# MicroController.net
KiCad netlist of a schematic drawn in Altium Designer
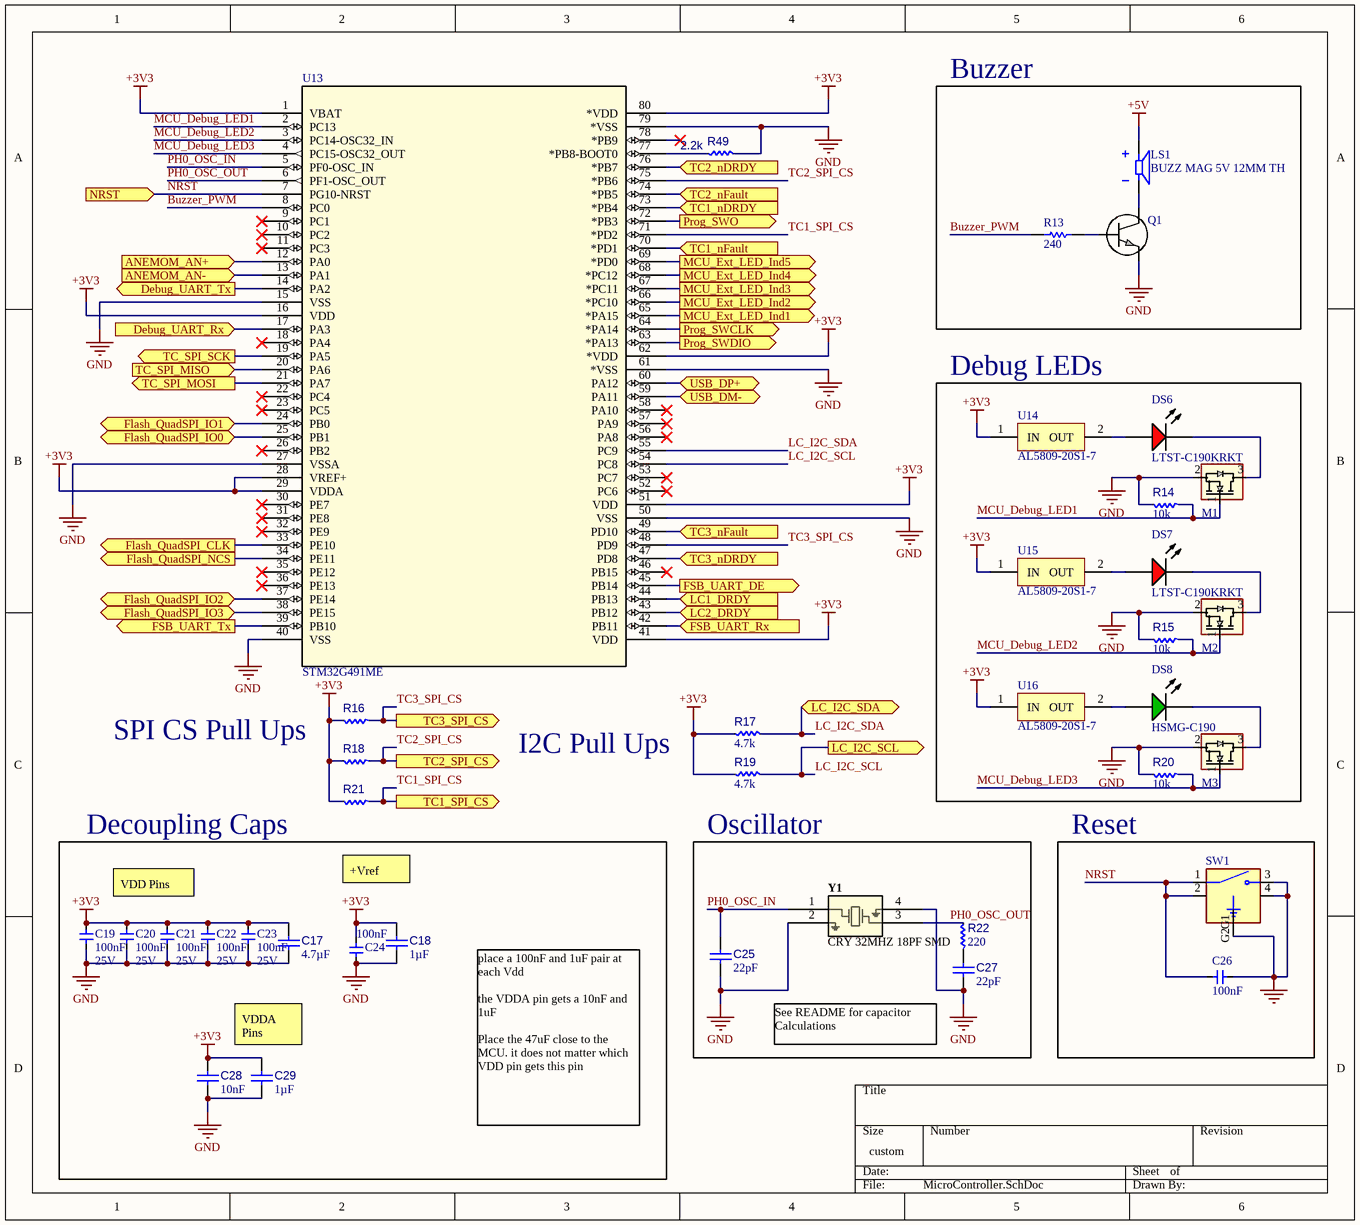
[diagram p0: MicroController.SchDoc]

(export (version "E")
  (design (tool "Eeschema 10.0.6"))
  (components
    (comp (ref "C17")
      (value "4.7µF")
      (footprint "Copy of CAPC0603(1608)100_L")
      (description "CC0603MRX5R6BB475 Chip Capacitor, 4.7µF +/-20%, 10V, 0603, Thickness 1 mm")
      (fields (field (name "TOLERANCE") "20%") (field (name "Comment") "CAP CER 4.7µF +/-20% 10V 0603"))
      (libsource (lib "University of Calgary - SOAR") (part "4.7uF"))
    )
    (comp (ref "C18")
      (value "1µF")
      (footprint "CAPC0402(1005)60_L")
      (description "Chip Capacitor, 1µF +/-20%, 10V, 0402, Thickness 0.6 mm")
      (fields (field (name "TOLERANCE") "10%") (field (name "Comment") "Capacitor 1µF +/-20% 10V 0402"))
      (libsource (lib "University of Calgary - SOAR") (part "CAP-NP-2"))
    )
    (comp (ref "C19")
      (value "100nF")
      (footprint "0.1uF-FP-CGA3E-0_3-0_1-IPC_A")
      (description "CGA3E2X7R1E104K080AA CAP CER 0.1UF 25V X7R 0603")
      (fields
        (field (name "MANUFACTURER") "TDK Corporation")
        (field (name "MANUFACTURER PART NUMBER") "CGA3E2X7R1E104K080AA")
        (field (name "VOLTAGE - RATED") "25V")
        (field (name "SOURCE") "PlumBay_SchLib.SchLib")
      )
      (libsource (lib "University of Calgary - SOAR") (part "100nF"))
    )
    (comp (ref "C20")
      (value "100nF")
      (footprint "0.1uF-FP-CGA3E-0_3-0_1-IPC_A")
      (description "CGA3E2X7R1E104K080AA CAP CER 0.1UF 25V X7R 0603")
      (fields
        (field (name "MANUFACTURER") "TDK Corporation")
        (field (name "MANUFACTURER PART NUMBER") "CGA3E2X7R1E104K080AA")
        (field (name "VOLTAGE - RATED") "25V")
        (field (name "SOURCE") "PlumBay_SchLib.SchLib")
      )
      (libsource (lib "University of Calgary - SOAR") (part "100nF"))
    )
    (comp (ref "C21")
      (value "100nF")
      (footprint "0.1uF-FP-CGA3E-0_3-0_1-IPC_A")
      (description "CGA3E2X7R1E104K080AA CAP CER 0.1UF 25V X7R 0603")
      (fields
        (field (name "MANUFACTURER") "TDK Corporation")
        (field (name "MANUFACTURER PART NUMBER") "CGA3E2X7R1E104K080AA")
        (field (name "VOLTAGE - RATED") "25V")
        (field (name "SOURCE") "PlumBay_SchLib.SchLib")
      )
      (libsource (lib "University of Calgary - SOAR") (part "100nF"))
    )
    (comp (ref "C22")
      (value "100nF")
      (footprint "0.1uF-FP-CGA3E-0_3-0_1-IPC_A")
      (description "CGA3E2X7R1E104K080AA CAP CER 0.1UF 25V X7R 0603")
      (fields
        (field (name "MANUFACTURER") "TDK Corporation")
        (field (name "MANUFACTURER PART NUMBER") "CGA3E2X7R1E104K080AA")
        (field (name "VOLTAGE - RATED") "25V")
        (field (name "SOURCE") "PlumBay_SchLib.SchLib")
      )
      (libsource (lib "University of Calgary - SOAR") (part "100nF"))
    )
    (comp (ref "C23")
      (value "100nF")
      (footprint "0.1uF-FP-CGA3E-0_3-0_1-IPC_A")
      (description "CGA3E2X7R1E104K080AA CAP CER 0.1UF 25V X7R 0603")
      (fields
        (field (name "MANUFACTURER") "TDK Corporation")
        (field (name "MANUFACTURER PART NUMBER") "CGA3E2X7R1E104K080AA")
        (field (name "VOLTAGE - RATED") "25V")
        (field (name "SOURCE") "PlumBay_SchLib.SchLib")
      )
      (libsource (lib "University of Calgary - SOAR") (part "100nF"))
    )
    (comp (ref "C24")
      (value "100nF")
      (footprint "0.1uF-FP-CGA3E-0_3-0_1-IPC_A")
      (description "CGA3E2X7R1E104K080AA CAP CER 0.1UF 25V X7R 0603")
      (fields
        (field (name "TOLERANCE") "10%")
        (field (name "MANUFACTURER") "TDK Corporation")
        (field (name "SOURCE") "PlumBay_SchLib.SchLib")
      )
      (libsource (lib "University of Calgary - SOAR") (part "100nF"))
    )
    (comp (ref "C25")
      (value "22pF")
      (footprint "CAP_0603_LD")
      (description "GRM1885C1H220JA01D - 22 pF ±5% 50V Ceramic Capacitor C0G, NP0 0603 (1608 Metric)")
      (fields (field (name "TOLERANCE") "5%") (field (name "VOLTAGE") "50V"))
      (libsource (lib "University of Calgary - SOAR") (part "CAP-NP-2"))
    )
    (comp (ref "C26")
      (value "100nF")
      (footprint "0.1uF-FP-CGA3E-0_3-0_1-IPC_A")
      (description "CGA3E2X7R1E104K080AA CAP CER 0.1UF 25V X7R 0603")
      (fields
        (field (name "TOLERANCE") "10%")
        (field (name "MANUFACTURER") "TDK Corporation")
        (field (name "SOURCE") "PlumBay_SchLib.SchLib")
      )
      (libsource (lib "University of Calgary - SOAR") (part "100nF"))
    )
    (comp (ref "C27")
      (value "22pF")
      (footprint "CAP_0603_LD")
      (description "GRM1885C1H220JA01D - 22 pF ±5% 50V Ceramic Capacitor C0G, NP0 0603 (1608 Metric)")
      (fields (field (name "TOLERANCE") "5%") (field (name "VOLTAGE") "50V"))
      (libsource (lib "University of Calgary - SOAR") (part "CAP-NP-2"))
    )
    (comp (ref "C28")
      (value "10nF")
      (footprint "CAP_0603")
      (description "C0603C103K5RACTU - Multilayer Ceramic Capacitors Mlcc - Smd/Smt 50V 0.01Uf X7R 0603 10%")
      (fields (field (name "TOLERANCE") "10%") (field (name "Comment") "CAP CER 10nF 50V 10% 0603"))
      (libsource (lib "University of Calgary - SOAR") (part "CAP-NP-2"))
    )
    (comp (ref "C29")
      (value "1µF")
      (footprint "CAPC0402(1005)60_L")
      (description "Chip Capacitor, 1µF +/-20%, 10V, 0402, Thickness 0.6 mm")
      (fields (field (name "TOLERANCE") "10%") (field (name "Comment") "Capacitor 1µF +/-20% 10V 0402"))
      (libsource (lib "University of Calgary - SOAR") (part "CAP-NP-2"))
    )
    (comp (ref "DS6")
      (value "LTST-C190KRKT")
      (footprint "LTST-C191KRKT_V")
      (description "LED Uni-Color Red, 62.5 mW, 25 mA, -30 to 85 degC, 2-Pin SMD, RoHS, Tape and Reel")
      (fields (field (name "POWER") "75mW") (field (name "MANUFACTURER") "Lite-On"))
      (libsource (lib "University of Calgary - SOAR") (part "LED-RED-AK-2"))
    )
    (comp (ref "DS7")
      (value "LTST-C190KRKT")
      (footprint "LTST-C191KRKT_V")
      (description "LED Uni-Color Red, 62.5 mW, 25 mA, -30 to 85 degC, 2-Pin SMD, RoHS, Tape and Reel")
      (fields (field (name "POWER") "75mW") (field (name "MANUFACTURER") "Lite-On"))
      (libsource (lib "University of Calgary - SOAR") (part "LED-RED-AK-2"))
    )
    (comp (ref "DS8")
      (value "HSMG-C190")
      (footprint "AVAG-HSMX-C190_V")
      (description "LED Uni-Color Green, 52 mW, 20 mA, -40 to 85 degC, 2-Pin SMD, RoHS, Tape and Reel")
      (fields (field (name "POWER") "52mW") (field (name "MANUFACTURER") "Avago"))
      (libsource (lib "University of Calgary - SOAR") (part "LED-GREEN-AK-2"))
    )
    (comp (ref "LS1")
      (value "BUZZ MAG 5V 12MM TH")
      (footprint "CMI-1210-5-95T-Footprint-1")
      (description "CMI-1210-5-95T 12 mm, 5 Vdc, 98 dB, Through Hole, Magnetic Audio Indicator Buzzer CMI-1210-5-95T")
      (libsource (lib "University of Calgary - SOAR") (part "CMI-1210-5-95T-Symbol-1"))
    )
    (comp (ref "M1")
      (value "MOS NMOS 30V 5.6A SOT-23")
      (footprint "PJA3404_R1_00001-Footprint-1")
      (libsource (lib "University of Calgary - SOAR") (part "TRANS-NPN-3"))
    )
    (comp (ref "M2")
      (value "MOS NMOS 30V 5.6A SOT-23")
      (footprint "PJA3404_R1_00001-Footprint-1")
      (libsource (lib "University of Calgary - SOAR") (part "TRANS-NPN-3"))
    )
    (comp (ref "M3")
      (value "MOS NMOS 30V 5.6A SOT-23")
      (footprint "PJA3404_R1_00001-Footprint-1")
      (libsource (lib "University of Calgary - SOAR") (part "TRANS-NPN-3"))
    )
    (comp (ref "Q1")
      (value "NPN 350mW 40V 200mA")
      (footprint "MMBT3904-TP-Footprint-1")
      (description "Transistor, Bipolar, Si, NPN, Amplifier, Small Signal, Vceo 40VDC, IC 200MA, Pd 350MW")
      (libsource (lib "University of Calgary - SOAR") (part "MMBT3904-TP-Symbol-1"))
    )
    (comp (ref "R13")
      (value "240")
      (footprint "RESC1005X40X25ML05T05")
      (description "Chip Resistor, 240 Ohm, +/- 5%, 100 mW, -55 to 155 degC, 0402 (1005 Metric), RoHS, Tape and Reel")
      (fields
        (field (name "PARTNUMBER") "ERJ-2GEJ241x")
        (field (name "TOLERANCE") "5%")
        (field (name "SOURCE") "PC4-SODIMM_V200_RC_A1_20141015.SCHLIB")
      )
      (libsource (lib "University of Calgary - SOAR") (part "CMP-2004-03155-3"))
    )
    (comp (ref "R14")
      (value "10k")
      (footprint "RESC2013X50X35ML15T15")
      (description "Chip Resistor, 10 KOhm, +/- 1%, 125 mW, -55 to 155 degC, 0805 (2012 Metric)")
      (fields (field (name "POWER") "125mW") (field (name "TOLERANCE") "1%"))
      (libsource (lib "University of Calgary - SOAR") (part "RES-2"))
    )
    (comp (ref "R15")
      (value "10k")
      (footprint "RESC2013X50X35ML15T15")
      (description "Chip Resistor, 10 KOhm, +/- 1%, 125 mW, -55 to 155 degC, 0805 (2012 Metric)")
      (fields (field (name "POWER") "125mW") (field (name "TOLERANCE") "1%"))
      (libsource (lib "University of Calgary - SOAR") (part "RES-2"))
    )
    (comp (ref "R16")
      (value "CRGCQ0603F2K2")
      (footprint "FP-CRGCQ0603-IPC_A")
      (libsource (lib "University of Calgary - SOAR") (part "RES-2"))
    )
    (comp (ref "R17")
      (value "4.7k")
      (footprint "RESC2013X70X40ML20T20")
      (description "Chip Resistor, 4.7 KOhm, +/- 1%, 0.125 W, -55 to 155 degC, 0805 (2012 Metric)")
      (fields (field (name "POWER") "125mW") (field (name "TOLERANCE") "1%"))
      (libsource (lib "University of Calgary - SOAR") (part "RES-2"))
    )
    (comp (ref "R18")
      (value "CRGCQ0603F2K2")
      (footprint "FP-CRGCQ0603-IPC_A")
      (libsource (lib "University of Calgary - SOAR") (part "RES-2"))
    )
    (comp (ref "R19")
      (value "4.7k")
      (footprint "RESC2013X70X40ML20T20")
      (description "Chip Resistor, 4.7 KOhm, +/- 1%, 0.125 W, -55 to 155 degC, 0805 (2012 Metric)")
      (fields (field (name "POWER") "125mW") (field (name "TOLERANCE") "1%"))
      (libsource (lib "University of Calgary - SOAR") (part "RES-2"))
    )
    (comp (ref "R20")
      (value "10k")
      (footprint "RESC2013X50X35ML15T15")
      (description "Chip Resistor, 10 KOhm, +/- 1%, 125 mW, -55 to 155 degC, 0805 (2012 Metric)")
      (fields (field (name "POWER") "125mW") (field (name "TOLERANCE") "1%"))
      (libsource (lib "University of Calgary - SOAR") (part "RES-2"))
    )
    (comp (ref "R21")
      (value "CRGCQ0603F2K2")
      (footprint "FP-CRGCQ0603-IPC_A")
      (libsource (lib "University of Calgary - SOAR") (part "RES-2"))
    )
    (comp (ref "R22")
      (value "220")
      (footprint "RES_0603_LD")
      (fields (field (name "Comment") "RES 220R 5% 100mW 0603"))
      (libsource (lib "University of Calgary - SOAR") (part "RES-2"))
    )
    (comp (ref "R49")
      (value "2.2k")
      (footprint "FP-CRGCQ0603-IPC_A")
      (libsource (lib "University of Calgary - SOAR") (part "RES-2"))
    )
    (comp (ref "SW1")
      (value "BTN 12V 0.05A PTS526SMG15SMTR2 LFS")
      (footprint "PTS526SMG15SMTR2-Footprint-1")
      (libsource (lib "University of Calgary - SOAR") (part "PTS526SMG15SMTR2-Symbol-1"))
    )
    (comp (ref "U13")
      (value "STM32G491ME")
      (footprint "STM32G491ME-Footprint-1")
      (description "MCU 32-Bit ARM Cortex-M4 RISC 512kByte Flash 1.71V to 3.6V 80-Pin LQFP Tray")
      (libsource (lib "University of Calgary - SOAR") (part "STM32G491ME-Symbol-1"))
    )
    (comp (ref "U14")
      (value "AL5809-20S1-7")
      (footprint "DIOD-SOD123-A_V")
      (description "Led Driver, Cc/Linear, -40 To 125Deg C Rohs Compliant: Yes")
      (libsource (lib "University of Calgary - SOAR") (part "DIOD-AL5809-2"))
    )
    (comp (ref "U15")
      (value "AL5809-20S1-7")
      (footprint "DIOD-SOD123-A_V")
      (description "Led Driver, Cc/Linear, -40 To 125Deg C Rohs Compliant: Yes")
      (libsource (lib "University of Calgary - SOAR") (part "DIOD-AL5809-2"))
    )
    (comp (ref "U16")
      (value "AL5809-20S1-7")
      (footprint "DIOD-SOD123-A_V")
      (description "Led Driver, Cc/Linear, -40 To 125Deg C Rohs Compliant: Yes")
      (libsource (lib "University of Calgary - SOAR") (part "DIOD-AL5809-2"))
    )
    (comp (ref "Y1")
      (value "CRY 32MHZ 18PF SMD")
      (footprint "ABM8-32.000MHZ-B2-T-Footprint-1")
      (description "Crystal 32MHz ±20ppm (Tol) ±50ppm (Stability) 18pF FUND 40Ohm 4-Pin Ultra Mini-CSMD T/R")
      (libsource (lib "University of Calgary - SOAR") (part "E7343LF"))
    )
  )
  (nets
    (net (code "1") (name "+3V3") (class "Default")
      (node (ref "C17") (pin "2") (pinfunction "2_2") (pintype "passive"))
      (node (ref "C18") (pin "2") (pinfunction "2_2") (pintype "passive"))
      (node (ref "C19") (pin "2") (pinfunction "2_2") (pintype "passive"))
      (node (ref "C20") (pin "2") (pinfunction "2_2") (pintype "passive"))
      (node (ref "C21") (pin "2") (pinfunction "2_2") (pintype "passive"))
      (node (ref "C22") (pin "2") (pinfunction "2_2") (pintype "passive"))
      (node (ref "C23") (pin "2") (pinfunction "2_2") (pintype "passive"))
      (node (ref "C24") (pin "2") (pinfunction "2_2") (pintype "passive"))
      (node (ref "C28") (pin "2") (pinfunction "2_2") (pintype "passive"))
      (node (ref "C29") (pin "2") (pinfunction "2_2") (pintype "passive"))
      (node (ref "R16") (pin "2") (pinfunction "2_2") (pintype "passive"))
      (node (ref "R17") (pin "1") (pinfunction "1_1") (pintype "passive"))
      (node (ref "R18") (pin "2") (pinfunction "2_2") (pintype "passive"))
      (node (ref "R19") (pin "1") (pinfunction "1_1") (pintype "passive"))
      (node (ref "R21") (pin "2") (pinfunction "2_2") (pintype "passive"))
      (node (ref "U13") (pin "1") (pinfunction "VBAT_1") (pintype "passive"))
      (node (ref "U13") (pin "16") (pinfunction "VDD_16") (pintype "power_in"))
      (node (ref "U13") (pin "28") (pinfunction "VREF+_28") (pintype "power_in"))
      (node (ref "U13") (pin "29") (pinfunction "VDDA_29") (pintype "power_in"))
      (node (ref "U13") (pin "41") (pinfunction "VDD_41") (pintype "power_in"))
      (node (ref "U13") (pin "51") (pinfunction "VDD_51") (pintype "power_in"))
      (node (ref "U13") (pin "62") (pinfunction "*VDD_62") (pintype "power_in"))
      (node (ref "U13") (pin "80") (pinfunction "*VDD_80") (pintype "power_in"))
      (node (ref "U14") (pin "1") (pinfunction "IN_1") (pintype "passive"))
      (node (ref "U15") (pin "1") (pinfunction "IN_1") (pintype "passive"))
      (node (ref "U16") (pin "1") (pinfunction "IN_1") (pintype "passive"))
    )
    (net (code "2") (name "+5V") (class "Default")
      (node (ref "LS1") (pin "P") (pinfunction "P_P") (pintype "passive"))
    )
    (net (code "3") (name "/ANEMOM_AN+") (class "Default")
      (node (ref "U13") (pin "12") (pinfunction "PA0_12") (pintype "bidirectional"))
    )
    (net (code "4") (name "/ANEMOM_AN-") (class "Default")
      (node (ref "U13") (pin "13") (pinfunction "PA1_13") (pintype "bidirectional"))
    )
    (net (code "5") (name "/Buzzer_PWM") (class "Default")
      (node (ref "R13") (pin "1") (pinfunction "1_1") (pintype "passive"))
      (node (ref "U13") (pin "8") (pinfunction "PC0_8") (pintype "bidirectional"))
    )
    (net (code "6") (name "/Debug_UART_Rx") (class "Default")
      (node (ref "U13") (pin "17") (pinfunction "PA3_17") (pintype "bidirectional"))
    )
    (net (code "7") (name "/Debug_UART_Tx") (class "Default")
      (node (ref "U13") (pin "14") (pinfunction "PA2_14") (pintype "bidirectional"))
    )
    (net (code "8") (name "/FSB_UART_DE") (class "Default")
      (node (ref "U13") (pin "45") (pinfunction "PB14_45") (pintype "bidirectional"))
    )
    (net (code "9") (name "/FSB_UART_Rx") (class "Default")
      (node (ref "U13") (pin "42") (pinfunction "PB11_42") (pintype "bidirectional"))
    )
    (net (code "10") (name "/FSB_UART_Tx") (class "Default")
      (node (ref "U13") (pin "39") (pinfunction "PB10_39") (pintype "bidirectional"))
    )
    (net (code "11") (name "/Flash_QuadSPI_CLK") (class "Default")
      (node (ref "U13") (pin "33") (pinfunction "PE10_33") (pintype "bidirectional"))
    )
    (net (code "12") (name "/Flash_QuadSPI_IO0") (class "Default")
      (node (ref "U13") (pin "25") (pinfunction "PB1_25") (pintype "bidirectional"))
    )
    (net (code "13") (name "/Flash_QuadSPI_IO1") (class "Default")
      (node (ref "U13") (pin "24") (pinfunction "PB0_24") (pintype "bidirectional"))
    )
    (net (code "14") (name "/Flash_QuadSPI_IO2") (class "Default")
      (node (ref "U13") (pin "37") (pinfunction "PE14_37") (pintype "bidirectional"))
    )
    (net (code "15") (name "/Flash_QuadSPI_IO3") (class "Default")
      (node (ref "U13") (pin "38") (pinfunction "PE15_38") (pintype "bidirectional"))
    )
    (net (code "16") (name "/Flash_QuadSPI_NCS") (class "Default")
      (node (ref "U13") (pin "34") (pinfunction "PE11_34") (pintype "bidirectional"))
    )
    (net (code "17") (name "/LC1_DRDY") (class "Default")
      (node (ref "U13") (pin "44") (pinfunction "PB13_44") (pintype "bidirectional"))
    )
    (net (code "18") (name "/LC2_DRDY") (class "Default")
      (node (ref "U13") (pin "43") (pinfunction "PB12_43") (pintype "bidirectional"))
    )
    (net (code "19") (name "/LC_I2C_SCL") (class "Default")
      (node (ref "R19") (pin "2") (pinfunction "2_2") (pintype "passive"))
      (node (ref "U13") (pin "54") (pinfunction "PC8_54") (pintype "bidirectional"))
    )
    (net (code "20") (name "/LC_I2C_SDA") (class "Default")
      (node (ref "R17") (pin "2") (pinfunction "2_2") (pintype "passive"))
      (node (ref "U13") (pin "55") (pinfunction "PC9_55") (pintype "bidirectional"))
    )
    (net (code "21") (name "/MCU_Debug_LED1") (class "Default")
      (node (ref "M1") (pin "1") (pinfunction "1_1") (pintype "passive"))
      (node (ref "R14") (pin "1") (pinfunction "1_1") (pintype "passive"))
      (node (ref "U13") (pin "2") (pinfunction "PC13_2") (pintype "bidirectional"))
    )
    (net (code "22") (name "/MCU_Debug_LED2") (class "Default")
      (node (ref "M2") (pin "1") (pinfunction "1_1") (pintype "passive"))
      (node (ref "R15") (pin "1") (pinfunction "1_1") (pintype "passive"))
      (node (ref "U13") (pin "3") (pinfunction "PC14-OSC32_IN_3") (pintype "bidirectional"))
    )
    (net (code "23") (name "/MCU_Debug_LED3") (class "Default")
      (node (ref "M3") (pin "1") (pinfunction "1_1") (pintype "passive"))
      (node (ref "R20") (pin "1") (pinfunction "1_1") (pintype "passive"))
      (node (ref "U13") (pin "4") (pinfunction "PC15-OSC32_OUT_4") (pintype "output"))
    )
    (net (code "24") (name "/MCU_Ext_LED_Ind1") (class "Default")
      (node (ref "U13") (pin "65") (pinfunction "*PA15_65") (pintype "bidirectional"))
    )
    (net (code "25") (name "/MCU_Ext_LED_Ind2") (class "Default")
      (node (ref "U13") (pin "66") (pinfunction "*PC10_66") (pintype "bidirectional"))
    )
    (net (code "26") (name "/MCU_Ext_LED_Ind3") (class "Default")
      (node (ref "U13") (pin "67") (pinfunction "*PC11_67") (pintype "bidirectional"))
    )
    (net (code "27") (name "/MCU_Ext_LED_Ind4") (class "Default")
      (node (ref "U13") (pin "68") (pinfunction "*PC12_68") (pintype "bidirectional"))
    )
    (net (code "28") (name "/MCU_Ext_LED_Ind5") (class "Default")
      (node (ref "U13") (pin "69") (pinfunction "*PD0_69") (pintype "bidirectional"))
    )
    (net (code "29") (name "/NRST") (class "Default")
      (node (ref "C26") (pin "2") (pinfunction "2_2") (pintype "passive"))
      (node (ref "SW1") (pin "1") (pinfunction "COM_1") (pintype "passive"))
      (node (ref "SW1") (pin "2") (pinfunction "COM_2") (pintype "passive"))
      (node (ref "U13") (pin "7") (pinfunction "PG10-NRST_7") (pintype "passive"))
    )
    (net (code "30") (name "/PH0_OSC_IN") (class "Default")
      (node (ref "C25") (pin "2") (pinfunction "2_2") (pintype "passive"))
      (node (ref "U13") (pin "5") (pinfunction "PF0-OSC_IN_5") (pintype "bidirectional"))
      (node (ref "Y1") (pin "1") (pinfunction "1_1") (pintype "passive"))
    )
    (net (code "31") (name "/PH0_OSC_OUT") (class "Default")
      (node (ref "R22") (pin "2") (pinfunction "2_2") (pintype "passive"))
      (node (ref "U13") (pin "6") (pinfunction "PF1-OSC_OUT_6") (pintype "output"))
      (node (ref "Y1") (pin "3") (pinfunction "3_3") (pintype "passive"))
    )
    (net (code "32") (name "/Prog_SWCLK") (class "Default")
      (node (ref "U13") (pin "64") (pinfunction "*PA14_64") (pintype "bidirectional"))
    )
    (net (code "33") (name "/Prog_SWDIO") (class "Default")
      (node (ref "U13") (pin "63") (pinfunction "*PA13_63") (pintype "bidirectional"))
    )
    (net (code "34") (name "/Prog_SWO") (class "Default")
      (node (ref "U13") (pin "72") (pinfunction "*PB3_72") (pintype "bidirectional"))
    )
    (net (code "35") (name "/TC1_SPI_CS") (class "Default")
      (node (ref "R21") (pin "1") (pinfunction "1_1") (pintype "passive"))
      (node (ref "U13") (pin "71") (pinfunction "*PD2_71") (pintype "bidirectional"))
    )
    (net (code "36") (name "/TC1_nDRDY") (class "Default")
      (node (ref "U13") (pin "73") (pinfunction "*PB4_73") (pintype "bidirectional"))
    )
    (net (code "37") (name "/TC1_nFault") (class "Default")
      (node (ref "U13") (pin "70") (pinfunction "*PD1_70") (pintype "bidirectional"))
    )
    (net (code "38") (name "/TC2_SPI_CS") (class "Default")
      (node (ref "R18") (pin "1") (pinfunction "1_1") (pintype "passive"))
      (node (ref "U13") (pin "75") (pinfunction "*PB6_75") (pintype "bidirectional"))
    )
    (net (code "39") (name "/TC2_nDRDY") (class "Default")
      (node (ref "U13") (pin "76") (pinfunction "*PB7_76") (pintype "bidirectional"))
    )
    (net (code "40") (name "/TC2_nFault") (class "Default")
      (node (ref "U13") (pin "74") (pinfunction "*PB5_74") (pintype "bidirectional"))
    )
    (net (code "41") (name "/TC3_SPI_CS") (class "Default")
      (node (ref "R16") (pin "1") (pinfunction "1_1") (pintype "passive"))
      (node (ref "U13") (pin "48") (pinfunction "PD9_48") (pintype "bidirectional"))
    )
    (net (code "42") (name "/TC3_nDRDY") (class "Default")
      (node (ref "U13") (pin "47") (pinfunction "PD8_47") (pintype "bidirectional"))
    )
    (net (code "43") (name "/TC3_nFault") (class "Default")
      (node (ref "U13") (pin "49") (pinfunction "PD10_49") (pintype "bidirectional"))
    )
    (net (code "44") (name "/TC_SPI_MISO") (class "Default")
      (node (ref "U13") (pin "20") (pinfunction "PA6_20") (pintype "bidirectional"))
    )
    (net (code "45") (name "/TC_SPI_MOSI") (class "Default")
      (node (ref "U13") (pin "21") (pinfunction "PA7_21") (pintype "bidirectional"))
    )
    (net (code "46") (name "/TC_SPI_SCK") (class "Default")
      (node (ref "U13") (pin "19") (pinfunction "PA5_19") (pintype "bidirectional"))
    )
    (net (code "47") (name "/USB_DM-") (class "Default")
      (node (ref "U13") (pin "59") (pinfunction "PA11_59") (pintype "bidirectional"))
    )
    (net (code "48") (name "/USB_DP+") (class "Default")
      (node (ref "U13") (pin "60") (pinfunction "PA12_60") (pintype "bidirectional"))
    )
    (net (code "49") (name "GND") (class "Default")
      (node (ref "C17") (pin "1") (pinfunction "1_1") (pintype "passive"))
      (node (ref "C18") (pin "1") (pinfunction "1_1") (pintype "passive"))
      (node (ref "C19") (pin "1") (pinfunction "1_1") (pintype "passive"))
      (node (ref "C20") (pin "1") (pinfunction "1_1") (pintype "passive"))
      (node (ref "C21") (pin "1") (pinfunction "1_1") (pintype "passive"))
      (node (ref "C22") (pin "1") (pinfunction "1_1") (pintype "passive"))
      (node (ref "C23") (pin "1") (pinfunction "1_1") (pintype "passive"))
      (node (ref "C24") (pin "1") (pinfunction "1_1") (pintype "passive"))
      (node (ref "C25") (pin "1") (pinfunction "1_1") (pintype "passive"))
      (node (ref "C26") (pin "1") (pinfunction "1_1") (pintype "passive"))
      (node (ref "C27") (pin "1") (pinfunction "1_1") (pintype "passive"))
      (node (ref "C28") (pin "1") (pinfunction "1_1") (pintype "passive"))
      (node (ref "C29") (pin "1") (pinfunction "1_1") (pintype "passive"))
      (node (ref "M1") (pin "2") (pinfunction "2_2") (pintype "passive"))
      (node (ref "M2") (pin "2") (pinfunction "2_2") (pintype "passive"))
      (node (ref "M3") (pin "2") (pinfunction "2_2") (pintype "passive"))
      (node (ref "Q1") (pin "2") (pinfunction "C_2") (pintype "passive"))
      (node (ref "R14") (pin "2") (pinfunction "2_2") (pintype "passive"))
      (node (ref "R15") (pin "2") (pinfunction "2_2") (pintype "passive"))
      (node (ref "R20") (pin "2") (pinfunction "2_2") (pintype "passive"))
      (node (ref "R49") (pin "2") (pinfunction "2_2") (pintype "passive"))
      (node (ref "SW1") (pin "3") (pinfunction "NO_3") (pintype "passive"))
      (node (ref "SW1") (pin "4") (pinfunction "NO_4") (pintype "passive"))
      (node (ref "SW1") (pin "G2") (pinfunction "GND_G2") (pintype "power_in"))
      (node (ref "U13") (pin "15") (pinfunction "VSS_15") (pintype "power_in"))
      (node (ref "U13") (pin "27") (pinfunction "VSSA_27") (pintype "power_in"))
      (node (ref "U13") (pin "40") (pinfunction "VSS_40") (pintype "power_in"))
      (node (ref "U13") (pin "50") (pinfunction "VSS_50") (pintype "power_in"))
      (node (ref "U13") (pin "61") (pinfunction "*VSS_61") (pintype "power_in"))
      (node (ref "U13") (pin "79") (pinfunction "*VSS_79") (pintype "power_in"))
      (node (ref "Y1") (pin "2") (pinfunction "2_2") (pintype "passive"))
      (node (ref "Y1") (pin "4") (pinfunction "4_4") (pintype "passive"))
    )
    (net (code "50") (name "Net-(C27-Pad2)") (class "Default")
      (node (ref "C27") (pin "2") (pinfunction "2_2") (pintype "passive"))
      (node (ref "R22") (pin "1") (pinfunction "1_1") (pintype "passive"))
    )
    (net (code "51") (name "Net-(DS6-A)") (class "Default")
      (node (ref "DS6") (pin "1") (pinfunction "A_1") (pintype "passive"))
      (node (ref "U14") (pin "2") (pinfunction "OUT_2") (pintype "passive"))
    )
    (net (code "52") (name "Net-(DS6-K)") (class "Default")
      (node (ref "DS6") (pin "2") (pinfunction "K_2") (pintype "passive"))
      (node (ref "M1") (pin "3") (pinfunction "3_3") (pintype "passive"))
    )
    (net (code "53") (name "Net-(DS7-A)") (class "Default")
      (node (ref "DS7") (pin "1") (pinfunction "A_1") (pintype "passive"))
      (node (ref "U15") (pin "2") (pinfunction "OUT_2") (pintype "passive"))
    )
    (net (code "54") (name "Net-(DS7-K)") (class "Default")
      (node (ref "DS7") (pin "2") (pinfunction "K_2") (pintype "passive"))
      (node (ref "M2") (pin "3") (pinfunction "3_3") (pintype "passive"))
    )
    (net (code "55") (name "Net-(DS8-A)") (class "Default")
      (node (ref "DS8") (pin "1") (pinfunction "A_1") (pintype "passive"))
      (node (ref "U16") (pin "2") (pinfunction "OUT_2") (pintype "passive"))
    )
    (net (code "56") (name "Net-(DS8-K)") (class "Default")
      (node (ref "DS8") (pin "2") (pinfunction "K_2") (pintype "passive"))
      (node (ref "M3") (pin "3") (pinfunction "3_3") (pintype "passive"))
    )
    (net (code "57") (name "Net-(Q1-B)") (class "Default")
      (node (ref "Q1") (pin "1") (pinfunction "B_1") (pintype "passive"))
      (node (ref "R13") (pin "2") (pinfunction "2_2") (pintype "passive"))
    )
    (net (code "58") (name "Net-(Q1-E)") (class "Default")
      (node (ref "LS1") (pin "N") (pinfunction "N_N") (pintype "passive"))
      (node (ref "Q1") (pin "3") (pinfunction "E_3") (pintype "passive"))
    )
    (net (code "59") (name "Net-(U13-*PB8-BOOT0)") (class "Default")
      (node (ref "R49") (pin "1") (pinfunction "1_1") (pintype "passive"))
      (node (ref "U13") (pin "77") (pinfunction "*PB8-BOOT0_77") (pintype "bidirectional"))
    )
    (net (code "60") (name "unconnected-(SW1-GND-PadG1)") (class "Default")
      (node (ref "SW1") (pin "G1") (pinfunction "GND_G1") (pintype "power_in"))
    )
    (net (code "61") (name "unconnected-(U13-*PB9-Pad78)") (class "Default")
      (node (ref "U13") (pin "78") (pinfunction "*PB9_78") (pintype "bidirectional+no_connect"))
    )
    (net (code "62") (name "unconnected-(U13-PA4-Pad18)") (class "Default")
      (node (ref "U13") (pin "18") (pinfunction "PA4_18") (pintype "bidirectional+no_connect"))
    )
    (net (code "63") (name "unconnected-(U13-PA8-Pad56)") (class "Default")
      (node (ref "U13") (pin "56") (pinfunction "PA8_56") (pintype "bidirectional+no_connect"))
    )
    (net (code "64") (name "unconnected-(U13-PA9-Pad57)") (class "Default")
      (node (ref "U13") (pin "57") (pinfunction "PA9_57") (pintype "bidirectional+no_connect"))
    )
    (net (code "65") (name "unconnected-(U13-PA10-Pad58)") (class "Default")
      (node (ref "U13") (pin "58") (pinfunction "PA10_58") (pintype "bidirectional+no_connect"))
    )
    (net (code "66") (name "unconnected-(U13-PB2-Pad26)") (class "Default")
      (node (ref "U13") (pin "26") (pinfunction "PB2_26") (pintype "bidirectional+no_connect"))
    )
    (net (code "67") (name "unconnected-(U13-PB15-Pad46)") (class "Default")
      (node (ref "U13") (pin "46") (pinfunction "PB15_46") (pintype "bidirectional+no_connect"))
    )
    (net (code "68") (name "unconnected-(U13-PC1-Pad9)") (class "Default")
      (node (ref "U13") (pin "9") (pinfunction "PC1_9") (pintype "bidirectional+no_connect"))
    )
    (net (code "69") (name "unconnected-(U13-PC2-Pad10)") (class "Default")
      (node (ref "U13") (pin "10") (pinfunction "PC2_10") (pintype "bidirectional+no_connect"))
    )
    (net (code "70") (name "unconnected-(U13-PC3-Pad11)") (class "Default")
      (node (ref "U13") (pin "11") (pinfunction "PC3_11") (pintype "bidirectional+no_connect"))
    )
    (net (code "71") (name "unconnected-(U13-PC4-Pad22)") (class "Default")
      (node (ref "U13") (pin "22") (pinfunction "PC4_22") (pintype "bidirectional+no_connect"))
    )
    (net (code "72") (name "unconnected-(U13-PC5-Pad23)") (class "Default")
      (node (ref "U13") (pin "23") (pinfunction "PC5_23") (pintype "bidirectional+no_connect"))
    )
    (net (code "73") (name "unconnected-(U13-PC6-Pad52)") (class "Default")
      (node (ref "U13") (pin "52") (pinfunction "PC6_52") (pintype "bidirectional+no_connect"))
    )
    (net (code "74") (name "unconnected-(U13-PC7-Pad53)") (class "Default")
      (node (ref "U13") (pin "53") (pinfunction "PC7_53") (pintype "bidirectional+no_connect"))
    )
    (net (code "75") (name "unconnected-(U13-PE7-Pad30)") (class "Default")
      (node (ref "U13") (pin "30") (pinfunction "PE7_30") (pintype "bidirectional+no_connect"))
    )
    (net (code "76") (name "unconnected-(U13-PE8-Pad31)") (class "Default")
      (node (ref "U13") (pin "31") (pinfunction "PE8_31") (pintype "bidirectional+no_connect"))
    )
    (net (code "77") (name "unconnected-(U13-PE9-Pad32)") (class "Default")
      (node (ref "U13") (pin "32") (pinfunction "PE9_32") (pintype "bidirectional+no_connect"))
    )
    (net (code "78") (name "unconnected-(U13-PE12-Pad35)") (class "Default")
      (node (ref "U13") (pin "35") (pinfunction "PE12_35") (pintype "bidirectional+no_connect"))
    )
    (net (code "79") (name "unconnected-(U13-PE13-Pad36)") (class "Default")
      (node (ref "U13") (pin "36") (pinfunction "PE13_36") (pintype "bidirectional+no_connect"))
    )
  )
)
